# Energy_meter1.net
KiCad netlist of a schematic drawn in EAGLE
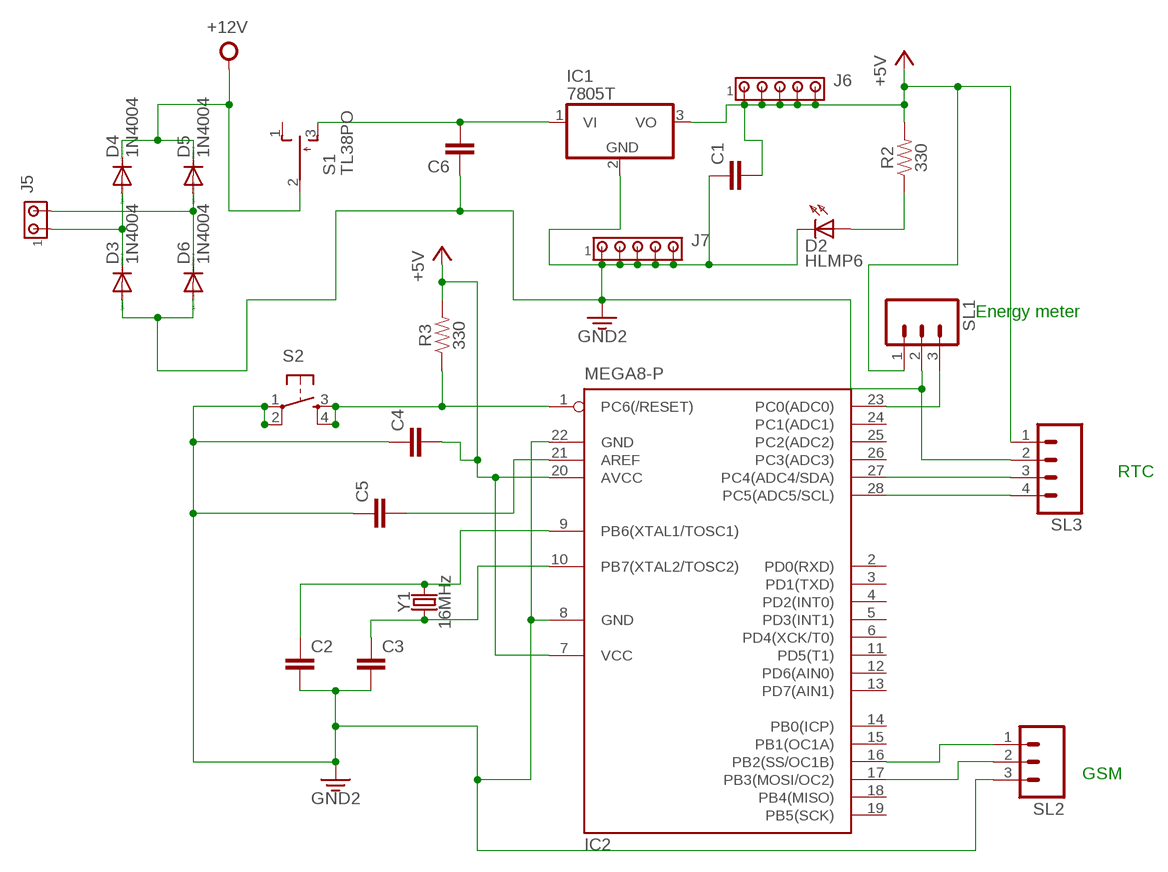
[diagram p0: schematic, sheet 1]

(export (version "E")
  (design (tool "Eeschema 10.0.6"))
  (components
    (comp (ref "C1")
      (value "C5/2.5")
      (footprint "eagle-import:C5B2.5")
      (libsource (lib "eagle-import") (part "C5/2.5"))
    )
    (comp (ref "C2")
      (value "C5/2.5")
      (footprint "eagle-import:C5B2.5")
      (libsource (lib "eagle-import") (part "C5/2.5"))
    )
    (comp (ref "C3")
      (value "C5/2.5")
      (footprint "eagle-import:C5B2.5")
      (libsource (lib "eagle-import") (part "C5/2.5"))
    )
    (comp (ref "C4")
      (value "C5/2.5")
      (footprint "eagle-import:C5B2.5")
      (libsource (lib "eagle-import") (part "C5/2.5"))
    )
    (comp (ref "C5")
      (value "C5/2.5")
      (footprint "eagle-import:C5B2.5")
      (libsource (lib "eagle-import") (part "C5/2.5"))
    )
    (comp (ref "C6")
      (value "C5/2.5")
      (footprint "eagle-import:C5B2.5")
      (libsource (lib "eagle-import") (part "C5/2.5"))
    )
    (comp (ref "D2")
      (value "HLMP6")
      (footprint "eagle-import:HLMP6")
      (fields (field (name "MF") "AGILENT TECHNOLOGIES") (field (name "MPN") "HLMP-6500"))
      (libsource (lib "eagle-import") (part "HLMP6"))
    )
    (comp (ref "D3")
      (value "1N4004")
      (footprint "eagle-import:DO41-10")
      (libsource (lib "eagle-import") (part "1N4004"))
    )
    (comp (ref "D4")
      (value "1N4004")
      (footprint "eagle-import:DO41-10")
      (libsource (lib "eagle-import") (part "1N4004"))
    )
    (comp (ref "D5")
      (value "1N4004")
      (footprint "eagle-import:DO41-10")
      (libsource (lib "eagle-import") (part "1N4004"))
    )
    (comp (ref "D6")
      (value "1N4004")
      (footprint "eagle-import:DO41-10")
      (libsource (lib "eagle-import") (part "1N4004"))
    )
    (comp (ref "IC1")
      (value "7805T")
      (footprint "eagle-import:TO220H")
      (libsource (lib "eagle-import") (part "78T05"))
    )
    (comp (ref "IC2")
      (value "MEGA8-P")
      (footprint "eagle-import:DIL28-3")
      (libsource (lib "eagle-import") (part "MEGA8-P"))
    )
    (comp (ref "J5")
      (value "MTA02-156")
      (footprint "eagle-import:1X2MTA")
      (libsource (lib "eagle-import") (part "MTA02-156"))
    )
    (comp (ref "J6")
      (value "MTA05-100")
      (footprint "eagle-import:10X05MTA")
      (libsource (lib "eagle-import") (part "MTA05-100"))
    )
    (comp (ref "J7")
      (value "MTA05-100")
      (footprint "eagle-import:10X05MTA")
      (libsource (lib "eagle-import") (part "MTA05-100"))
    )
    (comp (ref "R2")
      (value "330")
      (footprint "eagle-import:AXIAL-0.3")
      (libsource (lib "eagle-import") (part "330OHM-HORIZ-1/10W-5%"))
    )
    (comp (ref "R3")
      (value "330")
      (footprint "eagle-import:AXIAL-0.3")
      (libsource (lib "eagle-import") (part "330OHM-HORIZ-1/10W-5%"))
    )
    (comp (ref "S1")
      (value "TL38PO")
      (footprint "eagle-import:TL3XPO")
      (libsource (lib "eagle-import") (part "TL38PO"))
    )
    (comp (ref "S2")
      (value "TAC_SWITCHPTH")
      (footprint "eagle-import:TACTILE-PTH")
      (libsource (lib "eagle-import") (part "TAC_SWITCHPTH"))
    )
    (comp (ref "SL1")
      (value "MA03")
      (footprint "eagle-import:03P")
      (libsource (lib "eagle-import") (part "MA03"))
    )
    (comp (ref "SL2")
      (value "MA03")
      (footprint "eagle-import:03P")
      (libsource (lib "eagle-import") (part "MA03"))
    )
    (comp (ref "SL3")
      (value "MA04")
      (footprint "eagle-import:04PA")
      (libsource (lib "eagle-import") (part "MA04"))
    )
    (comp (ref "Y1")
      (value "16MHz")
      (footprint "eagle-import:HC49US")
      (libsource (lib "eagle-import") (part "CRYSTAL-16MHZPTH-HC49US"))
    )
  )
  (nets
    (net (code "1") (name "+5V") (class "Default")
      (node (ref "C1") (pin "2") (pinfunction "2_2") (pintype "passive"))
      (node (ref "C4") (pin "2") (pinfunction "2_2") (pintype "passive"))
      (node (ref "IC1") (pin "3") (pinfunction "VO_3") (pintype "passive"))
      (node (ref "IC2") (pin "20") (pinfunction "AVCC_20") (pintype "power_in"))
      (node (ref "IC2") (pin "7") (pinfunction "VCC_7") (pintype "power_in"))
      (node (ref "J6") (pin "1") (pinfunction "1_1") (pintype "passive"))
      (node (ref "J6") (pin "2") (pinfunction "2_2") (pintype "passive"))
      (node (ref "J6") (pin "3") (pinfunction "3_3") (pintype "passive"))
      (node (ref "J6") (pin "4") (pinfunction "4_4") (pintype "passive"))
      (node (ref "J6") (pin "5") (pinfunction "5_5") (pintype "passive"))
      (node (ref "R2") (pin "P$2") (pinfunction "2_P$2") (pintype "passive"))
      (node (ref "R3") (pin "P$2") (pinfunction "2_P$2") (pintype "passive"))
      (node (ref "SL1") (pin "1") (pinfunction "1_1") (pintype "passive"))
      (node (ref "SL3") (pin "1") (pinfunction "1_1") (pintype "passive"))
    )
    (net (code "2") (name "+12V") (class "Default")
      (node (ref "D4") (pin "C") (pinfunction "C_C") (pintype "passive"))
      (node (ref "D5") (pin "C") (pinfunction "C_C") (pintype "passive"))
      (node (ref "S1") (pin "2") (pinfunction "P_2") (pintype "passive"))
    )
    (net (code "3") (name "GND2") (class "Default")
      (node (ref "C1") (pin "1") (pinfunction "1_1") (pintype "passive"))
      (node (ref "C2") (pin "2") (pinfunction "2_2") (pintype "passive"))
      (node (ref "C3") (pin "2") (pinfunction "2_2") (pintype "passive"))
      (node (ref "C4") (pin "1") (pinfunction "1_1") (pintype "passive"))
      (node (ref "C5") (pin "1") (pinfunction "1_1") (pintype "passive"))
      (node (ref "C6") (pin "1") (pinfunction "1_1") (pintype "passive"))
      (node (ref "D2") (pin "K") (pinfunction "K_K") (pintype "passive"))
      (node (ref "D3") (pin "A") (pinfunction "A_A") (pintype "passive"))
      (node (ref "D6") (pin "A") (pinfunction "A_A") (pintype "passive"))
      (node (ref "IC1") (pin "2") (pinfunction "GND_2") (pintype "passive"))
      (node (ref "IC2") (pin "22") (pinfunction "GND_22") (pintype "power_in"))
      (node (ref "IC2") (pin "8") (pinfunction "GND_8") (pintype "power_in"))
      (node (ref "J7") (pin "1") (pinfunction "1_1") (pintype "passive"))
      (node (ref "J7") (pin "2") (pinfunction "2_2") (pintype "passive"))
      (node (ref "J7") (pin "3") (pinfunction "3_3") (pintype "passive"))
      (node (ref "J7") (pin "4") (pinfunction "4_4") (pintype "passive"))
      (node (ref "J7") (pin "5") (pinfunction "5_5") (pintype "passive"))
      (node (ref "S2") (pin "1") (pinfunction "1_1") (pintype "passive"))
      (node (ref "S2") (pin "2") (pinfunction "2_2") (pintype "passive"))
      (node (ref "SL1") (pin "2") (pinfunction "2_2") (pintype "passive"))
      (node (ref "SL2") (pin "3") (pinfunction "3_3") (pintype "passive"))
      (node (ref "SL3") (pin "2") (pinfunction "2_2") (pintype "passive"))
    )
    (net (code "4") (name "Net-(D3-PadC)") (class "Default")
      (node (ref "D3") (pin "C") (pinfunction "C_C") (pintype "passive"))
      (node (ref "D4") (pin "A") (pinfunction "A_A") (pintype "passive"))
      (node (ref "J5") (pin "1") (pinfunction "1_1") (pintype "passive"))
    )
    (net (code "5") (name "Net-(D5-PadA)") (class "Default")
      (node (ref "D5") (pin "A") (pinfunction "A_A") (pintype "passive"))
      (node (ref "D6") (pin "C") (pinfunction "C_C") (pintype "passive"))
      (node (ref "J5") (pin "2") (pinfunction "2_2") (pintype "passive"))
    )
    (net (code "6") (name "Net-(IC1-VI)") (class "Default")
      (node (ref "C6") (pin "2") (pinfunction "2_2") (pintype "passive"))
      (node (ref "IC1") (pin "1") (pinfunction "VI_1") (pintype "input"))
      (node (ref "S1") (pin "3") (pinfunction "S_3") (pintype "passive"))
    )
    (net (code "7") (name "Net-(IC2-AREF)") (class "Default")
      (node (ref "C5") (pin "2") (pinfunction "2_2") (pintype "passive"))
      (node (ref "IC2") (pin "21") (pinfunction "AREF_21") (pintype "passive"))
    )
    (net (code "8") (name "Net-(IC2-PB2(SS{slash}OC1B))") (class "Default")
      (node (ref "IC2") (pin "16") (pinfunction "PB2(SS/OC1B)_16") (pintype "bidirectional"))
      (node (ref "SL2") (pin "1") (pinfunction "1_1") (pintype "passive"))
    )
    (net (code "9") (name "Net-(IC2-PB3(MOSI{slash}OC2))") (class "Default")
      (node (ref "IC2") (pin "17") (pinfunction "PB3(MOSI/OC2)_17") (pintype "bidirectional"))
      (node (ref "SL2") (pin "2") (pinfunction "2_2") (pintype "passive"))
    )
    (net (code "10") (name "Net-(IC2-PB6(XTAL1{slash}TOSC1))") (class "Default")
      (node (ref "C2") (pin "1") (pinfunction "1_1") (pintype "passive"))
      (node (ref "IC2") (pin "9") (pinfunction "PB6(XTAL1/TOSC1)_9") (pintype "bidirectional"))
      (node (ref "Y1") (pin "2") (pinfunction "2_2") (pintype "passive"))
    )
    (net (code "11") (name "Net-(IC2-PB7(XTAL2{slash}TOSC2))") (class "Default")
      (node (ref "C3") (pin "1") (pinfunction "1_1") (pintype "passive"))
      (node (ref "IC2") (pin "10") (pinfunction "PB7(XTAL2/TOSC2)_10") (pintype "bidirectional"))
      (node (ref "Y1") (pin "1") (pinfunction "1_1") (pintype "passive"))
    )
    (net (code "12") (name "Net-(IC2-PC0(ADC0))") (class "Default")
      (node (ref "IC2") (pin "23") (pinfunction "PC0(ADC0)_23") (pintype "bidirectional"))
      (node (ref "SL1") (pin "3") (pinfunction "3_3") (pintype "passive"))
    )
    (net (code "13") (name "Net-(IC2-PC4(ADC4{slash}SDA))") (class "Default")
      (node (ref "IC2") (pin "27") (pinfunction "PC4(ADC4/SDA)_27") (pintype "bidirectional"))
      (node (ref "SL3") (pin "3") (pinfunction "3_3") (pintype "passive"))
    )
    (net (code "14") (name "Net-(IC2-PC5(ADC5{slash}SCL))") (class "Default")
      (node (ref "IC2") (pin "28") (pinfunction "PC5(ADC5/SCL)_28") (pintype "bidirectional"))
      (node (ref "SL3") (pin "4") (pinfunction "4_4") (pintype "passive"))
    )
    (net (code "15") (name "Net-(IC2-PC6({slash}RESET))") (class "Default")
      (node (ref "IC2") (pin "1") (pinfunction "PC6(/RESET)_1") (pintype "bidirectional"))
      (node (ref "R3") (pin "P$1") (pinfunction "1_P$1") (pintype "passive"))
      (node (ref "S2") (pin "3") (pinfunction "3_3") (pintype "passive"))
      (node (ref "S2") (pin "4") (pinfunction "4_4") (pintype "passive"))
    )
    (net (code "16") (name "Net-(R2-1)") (class "Default")
      (node (ref "D2") (pin "A") (pinfunction "A_A") (pintype "passive"))
      (node (ref "R2") (pin "P$1") (pinfunction "1_P$1") (pintype "passive"))
    )
    (net (code "17") (name "unconnected-(IC2-PB0(ICP)-Pad14)") (class "Default")
      (node (ref "IC2") (pin "14") (pinfunction "PB0(ICP)_14") (pintype "bidirectional"))
    )
    (net (code "18") (name "unconnected-(IC2-PB1(OC1A)-Pad15)") (class "Default")
      (node (ref "IC2") (pin "15") (pinfunction "PB1(OC1A)_15") (pintype "bidirectional"))
    )
    (net (code "19") (name "unconnected-(IC2-PB4(MISO)-Pad18)") (class "Default")
      (node (ref "IC2") (pin "18") (pinfunction "PB4(MISO)_18") (pintype "bidirectional"))
    )
    (net (code "20") (name "unconnected-(IC2-PB5(SCK)-Pad19)") (class "Default")
      (node (ref "IC2") (pin "19") (pinfunction "PB5(SCK)_19") (pintype "bidirectional"))
    )
    (net (code "21") (name "unconnected-(IC2-PC1(ADC1)-Pad24)") (class "Default")
      (node (ref "IC2") (pin "24") (pinfunction "PC1(ADC1)_24") (pintype "bidirectional"))
    )
    (net (code "22") (name "unconnected-(IC2-PC2(ADC2)-Pad25)") (class "Default")
      (node (ref "IC2") (pin "25") (pinfunction "PC2(ADC2)_25") (pintype "bidirectional"))
    )
    (net (code "23") (name "unconnected-(IC2-PC3(ADC3)-Pad26)") (class "Default")
      (node (ref "IC2") (pin "26") (pinfunction "PC3(ADC3)_26") (pintype "bidirectional"))
    )
    (net (code "24") (name "unconnected-(IC2-PD0(RXD)-Pad2)") (class "Default")
      (node (ref "IC2") (pin "2") (pinfunction "PD0(RXD)_2") (pintype "bidirectional"))
    )
    (net (code "25") (name "unconnected-(IC2-PD1(TXD)-Pad3)") (class "Default")
      (node (ref "IC2") (pin "3") (pinfunction "PD1(TXD)_3") (pintype "bidirectional"))
    )
    (net (code "26") (name "unconnected-(IC2-PD2(INT0)-Pad4)") (class "Default")
      (node (ref "IC2") (pin "4") (pinfunction "PD2(INT0)_4") (pintype "bidirectional"))
    )
    (net (code "27") (name "unconnected-(IC2-PD3(INT1)-Pad5)") (class "Default")
      (node (ref "IC2") (pin "5") (pinfunction "PD3(INT1)_5") (pintype "bidirectional"))
    )
    (net (code "28") (name "unconnected-(IC2-PD4(XCK{slash}T0)-Pad6)") (class "Default")
      (node (ref "IC2") (pin "6") (pinfunction "PD4(XCK/T0)_6") (pintype "bidirectional"))
    )
    (net (code "29") (name "unconnected-(IC2-PD5(T1)-Pad11)") (class "Default")
      (node (ref "IC2") (pin "11") (pinfunction "PD5(T1)_11") (pintype "bidirectional"))
    )
    (net (code "30") (name "unconnected-(IC2-PD6(AIN0)-Pad12)") (class "Default")
      (node (ref "IC2") (pin "12") (pinfunction "PD6(AIN0)_12") (pintype "bidirectional"))
    )
    (net (code "31") (name "unconnected-(IC2-PD7(AIN1)-Pad13)") (class "Default")
      (node (ref "IC2") (pin "13") (pinfunction "PD7(AIN1)_13") (pintype "bidirectional"))
    )
    (net (code "32") (name "unconnected-(S1-O-Pad1)") (class "Default")
      (node (ref "S1") (pin "1") (pinfunction "O_1") (pintype "passive"))
    )
  )
)
